# MCU.net
KiCad netlist of a schematic drawn in Altium Designer
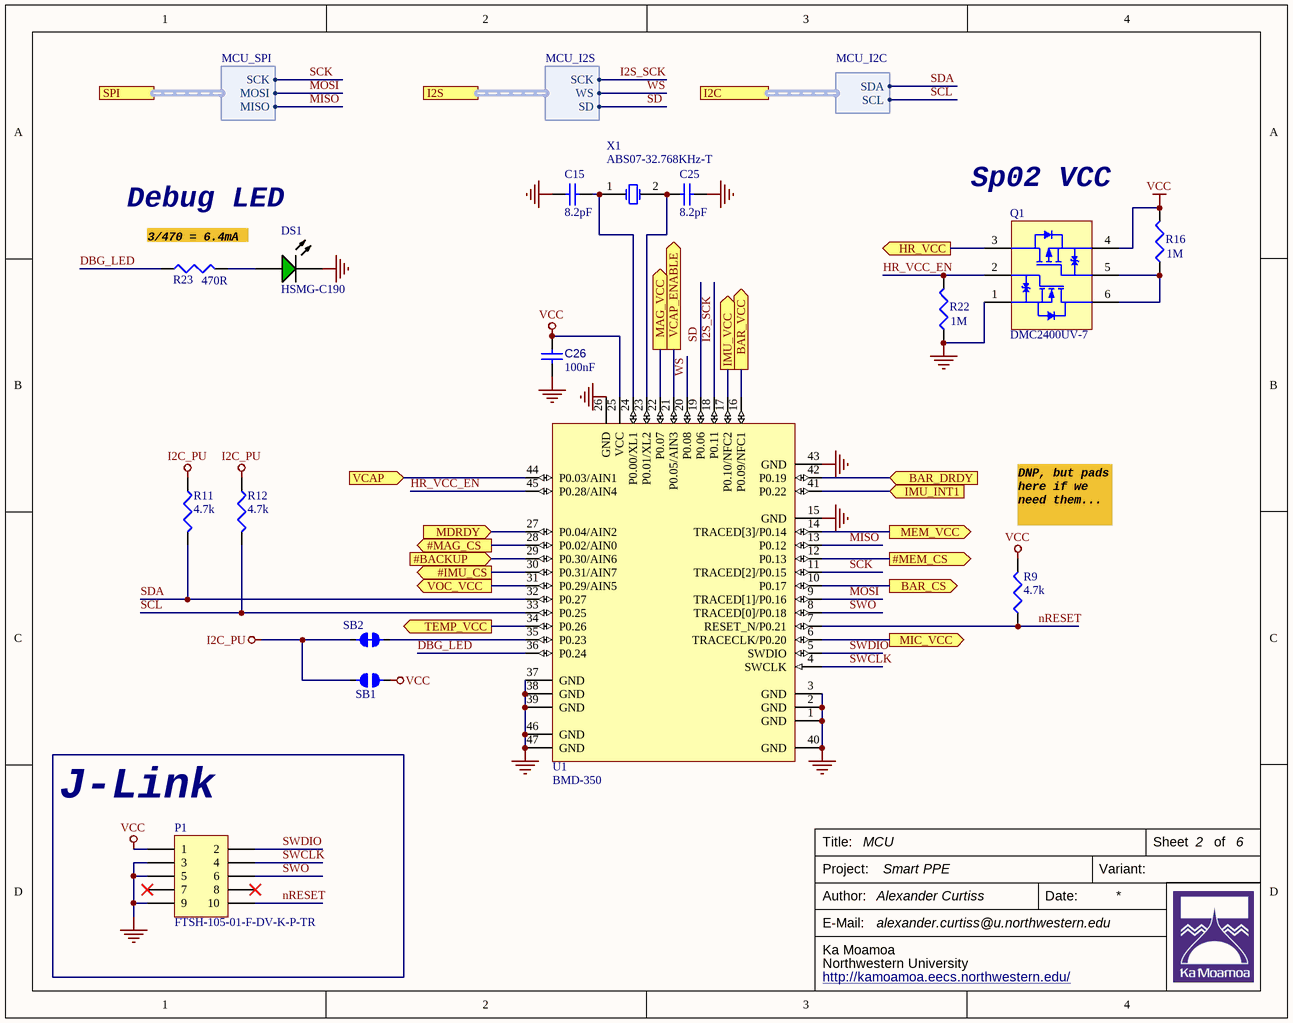
[diagram p0: MCU.SchDoc]

(export (version "E")
  (design (tool "Eeschema 10.0.6"))
  (components
    (comp (ref "C15")
      (value "8.2pF")
      (footprint "CAPC1005X56X25NL10T15")
      (fields
        (field (name "PART NUMBER") "04025A8R2JAT2A")
        (field (name "MANUFACTURER") "AVX Interconnect / Elco")
      )
      (libsource (lib "Altium Content Vault") (part "CAP"))
    )
    (comp (ref "C25")
      (value "8.2pF")
      (footprint "CAPC1005X56X25NL10T15")
      (fields
        (field (name "PART NUMBER") "04025A8R2JAT2A")
        (field (name "MANUFACTURER") "AVX Interconnect / Elco")
      )
      (libsource (lib "Altium Content Vault") (part "CAP"))
    )
    (comp (ref "C26")
      (value "100nF")
      (footprint "CAPC0402(1005)60_L")
      (description "Chip Capacitor, 100nF +/-20%, 25V, 0402, Thickness 0.6 mm")
      (fields (field (name "TOLERANCE") "10%") (field (name "Comment") "Capacitor 100nF +/-20% 25V 0402"))
      (libsource (lib "Ka Moamoa") (part "CAP-NP-2"))
    )
    (comp (ref "DS1")
      (value "HSMG-C190")
      (footprint "AVAG-HSMX-C190_V")
      (description "Chip LED, Green, 2.2 V, -40 to 85 degC, 2-Pin SMD, RoHS, Tape and Reel")
      (libsource (lib "Altium Content Vault") (part "LED-GREEN-AK-2"))
    )
    (comp (ref "P1")
      (value "FTSH-105-01-F-DV-K-P-TR")
      (footprint "FTSH-105-01-F-DV-K-P-TR-Footprint-1")
      (description "CONN HEADER SMD 10POS 1.27MM")
      (libsource (lib "Ka Moamoa") (part "FTSH-105-01-F-DV-K-P-TR"))
    )
    (comp (ref "Q1")
      (value "DMC2400UV-7")
      (footprint "DIOD-SOT563-6_V")
      (fields (field (name "MANUFACTURER") "Diodes Inc"))
      (libsource (lib "Altium Content Vault") (part "DIOD-DMC2400UV-SOT563-6"))
    )
    (comp (ref "R9")
      (value "4.7k")
      (footprint "RESC1608X55X25NL10T15")
      (description "Resistor 4.7kΩ 1% 0603")
      (fields (field (name "TOLERANCE") "1%"))
      (libsource (lib "Ka Moamoa") (part "RES"))
    )
    (comp (ref "R11")
      (value "4.7k")
      (footprint "RESC1608X55X25NL10T15")
      (description "Resistor 4.7kΩ 1% 0603")
      (fields (field (name "TOLERANCE") "1%"))
      (libsource (lib "Ka Moamoa") (part "RES"))
    )
    (comp (ref "R12")
      (value "4.7k")
      (footprint "RESC1608X55X25NL10T15")
      (description "Resistor 4.7kΩ 1% 0603")
      (fields (field (name "TOLERANCE") "1%"))
      (libsource (lib "Ka Moamoa") (part "RES"))
    )
    (comp (ref "R16")
      (value "1M")
      (footprint "RESC1608X55X25NL10T15")
      (description "Resistor =Value =Tolerance 0603")
      (fields (field (name "TOLERANCE") "1%"))
      (libsource (lib "Ka Moamoa") (part "RES"))
    )
    (comp (ref "R22")
      (value "1M")
      (footprint "RESC1608X55X25NL10T15")
      (description "Resistor =Value =Tolerance 0603")
      (fields (field (name "TOLERANCE") "1%"))
      (libsource (lib "Ka Moamoa") (part "RES"))
    )
    (comp (ref "R23")
      (value "470R")
      (footprint "RESC1608X55X25NL10T15")
      (description "Resistor 470Ω 1% 0603")
      (fields (field (name "TOLERANCE") "1%"))
      (libsource (lib "Ka Moamoa") (part "RES"))
    )
    (comp (ref "SB1")
      (value "Solder Bridge")
      (footprint "Solder Bridge-Footprint-1")
      (description "Normally open solder jumper")
      (libsource (lib "Ka Moamoa") (part "Solder Bridge"))
    )
    (comp (ref "SB2")
      (value "Solder Bridge NC")
      (footprint "Jumper NC-Footprint-1")
      (description "Normally closed solder jumper")
      (libsource (lib "Ka Moamoa") (part "Solder Bridge NC"))
    )
    (comp (ref "U1")
      (value "BMD-350")
      (footprint "BMD_LGA47S_865X640X150_CHIP")
      (description "u-blox BMD-350 Bluetooth 5 module")
      (fields (field (name "MANUFACTURER") "u-blox"))
      (libsource (lib "Ka Moamoa") (part "BMD-350"))
    )
    (comp (ref "X1")
      (value "ABS07-32.768KHz-T")
      (footprint "ABRA-ABS07-2_V")
      (description "Crystal, 32.768 kHz, 12.5 pF, -40 to 85 degC, SMD Low Profile 3.2 x 1.5 x 0.9 mm, Tape and Reel")
      (fields (field (name "MANUFACTURER") "Abracon"))
      (libsource (lib "Altium Content Vault") (part "ABRA-ABS07-2"))
    )
  )
  (nets
    (net (code "4") (name "/#BACKUP") (class "Default")
      (node (ref "U1") (pin "29") (pinfunction "P0.30/AIN6_29") (pintype "bidirectional"))
    )
    (net (code "5") (name "/#IMU_CS") (class "Default")
      (node (ref "U1") (pin "30") (pinfunction "P0.31/AIN7_30") (pintype "bidirectional"))
    )
    (net (code "6") (name "/#MAG_CS") (class "Default")
      (node (ref "U1") (pin "28") (pinfunction "P0.02/AIN0_28") (pintype "bidirectional"))
    )
    (net (code "7") (name "/#MEM_CS") (class "Default")
      (node (ref "U1") (pin "12") (pinfunction "P0.13_12") (pintype "bidirectional"))
    )
    (net (code "8") (name "/BAR_CS") (class "Default")
      (node (ref "U1") (pin "10") (pinfunction "P0.17_10") (pintype "bidirectional"))
    )
    (net (code "9") (name "/BAR_DRDY") (class "Default")
      (node (ref "U1") (pin "42") (pinfunction "P0.19_42") (pintype "bidirectional"))
    )
    (net (code "10") (name "/BAR_VCC") (class "Default")
      (node (ref "U1") (pin "16") (pinfunction "P0.09/NFC1_16") (pintype "bidirectional"))
    )
    (net (code "11") (name "/DBG_LED") (class "Default")
      (node (ref "R23") (pin "1") (pinfunction "1_1") (pintype "passive"))
      (node (ref "U1") (pin "36") (pinfunction "P0.24_36") (pintype "bidirectional"))
    )
    (net (code "12") (name "/HR_VCC") (class "Default")
      (node (ref "Q1") (pin "3") (pinfunction "D2_3") (pintype "passive"))
    )
    (net (code "13") (name "/HR_VCC_EN") (class "Default")
      (node (ref "Q1") (pin "2") (pinfunction "G1_2") (pintype "passive"))
      (node (ref "R22") (pin "2") (pinfunction "2_2") (pintype "passive"))
      (node (ref "U1") (pin "45") (pinfunction "P0.28/AIN4_45") (pintype "bidirectional"))
    )
    (net (code "14") (name "/I2S_SCK") (class "Default")
      (node (ref "U1") (pin "18") (pinfunction "P0.11_18") (pintype "bidirectional"))
    )
    (net (code "15") (name "/IMU_INT1") (class "Default")
      (node (ref "U1") (pin "41") (pinfunction "P0.22_41") (pintype "bidirectional"))
    )
    (net (code "16") (name "/IMU_VCC") (class "Default")
      (node (ref "U1") (pin "17") (pinfunction "P0.10/NFC2_17") (pintype "bidirectional"))
    )
    (net (code "17") (name "/MAG_VCC") (class "Default")
      (node (ref "U1") (pin "22") (pinfunction "P0.07_22") (pintype "bidirectional"))
    )
    (net (code "18") (name "/MDRDY") (class "Default")
      (node (ref "U1") (pin "27") (pinfunction "P0.04/AIN2_27") (pintype "bidirectional"))
    )
    (net (code "19") (name "/MEM_VCC") (class "Default")
      (node (ref "U1") (pin "14") (pinfunction "TRACED[3]/P0.14_14") (pintype "bidirectional"))
    )
    (net (code "20") (name "/MIC_VCC") (class "Default")
      (node (ref "U1") (pin "6") (pinfunction "TRACECLK/P0.20_6") (pintype "bidirectional"))
    )
    (net (code "21") (name "/MISO") (class "Default")
      (node (ref "U1") (pin "13") (pinfunction "P0.12_13") (pintype "bidirectional"))
    )
    (net (code "22") (name "/MOSI") (class "Default")
      (node (ref "U1") (pin "9") (pinfunction "TRACED[1]/P0.16_9") (pintype "bidirectional"))
    )
    (net (code "23") (name "/SCK") (class "Default")
      (node (ref "U1") (pin "11") (pinfunction "TRACED[2]/P0.15_11") (pintype "bidirectional"))
    )
    (net (code "24") (name "/SCL") (class "Default")
      (node (ref "R12") (pin "1") (pinfunction "1_1") (pintype "passive"))
      (node (ref "U1") (pin "33") (pinfunction "P0.25_33") (pintype "bidirectional"))
    )
    (net (code "25") (name "/SD") (class "Default")
      (node (ref "U1") (pin "19") (pinfunction "P0.06_19") (pintype "bidirectional"))
    )
    (net (code "26") (name "/SDA") (class "Default")
      (node (ref "R11") (pin "1") (pinfunction "1_1") (pintype "passive"))
      (node (ref "U1") (pin "32") (pinfunction "P0.27_32") (pintype "bidirectional"))
    )
    (net (code "27") (name "/SWCLK") (class "Default")
      (node (ref "P1") (pin "4") (pinfunction "4_4") (pintype "passive"))
      (node (ref "U1") (pin "4") (pinfunction "SWCLK_4") (pintype "input"))
    )
    (net (code "28") (name "/SWDIO") (class "Default")
      (node (ref "P1") (pin "2") (pinfunction "2_2") (pintype "passive"))
      (node (ref "U1") (pin "5") (pinfunction "SWDIO_5") (pintype "bidirectional"))
    )
    (net (code "29") (name "/SWO") (class "Default")
      (node (ref "P1") (pin "6") (pinfunction "6_6") (pintype "passive"))
      (node (ref "U1") (pin "8") (pinfunction "TRACED[0]/P0.18_8") (pintype "bidirectional"))
    )
    (net (code "30") (name "/TEMP_VCC") (class "Default")
      (node (ref "U1") (pin "34") (pinfunction "P0.26_34") (pintype "bidirectional"))
    )
    (net (code "31") (name "/VCAP") (class "Default")
      (node (ref "U1") (pin "44") (pinfunction "P0.03/AIN1_44") (pintype "bidirectional"))
    )
    (net (code "32") (name "/VCAP_ENABLE") (class "Default")
      (node (ref "U1") (pin "21") (pinfunction "P0.05/AIN3_21") (pintype "bidirectional"))
    )
    (net (code "33") (name "/VOC_VCC") (class "Default")
      (node (ref "U1") (pin "31") (pinfunction "P0.29/AIN5_31") (pintype "bidirectional"))
    )
    (net (code "34") (name "/WS") (class "Default")
      (node (ref "U1") (pin "20") (pinfunction "P0.08_20") (pintype "bidirectional"))
    )
    (net (code "35") (name "/nRESET") (class "Default")
      (node (ref "P1") (pin "10") (pinfunction "10_10") (pintype "passive"))
      (node (ref "R9") (pin "1") (pinfunction "1_1") (pintype "passive"))
      (node (ref "U1") (pin "7") (pinfunction "RESET_N/P0.21_7") (pintype "bidirectional"))
    )
    (net (code "39") (name "GND") (class "Default")
      (node (ref "C15") (pin "1") (pinfunction "1_1") (pintype "passive"))
      (node (ref "C25") (pin "1") (pinfunction "1_1") (pintype "passive"))
      (node (ref "C26") (pin "2") (pinfunction "2_2") (pintype "passive"))
      (node (ref "DS1") (pin "2") (pinfunction "K_2") (pintype "passive"))
      (node (ref "P1") (pin "3") (pinfunction "3_3") (pintype "passive"))
      (node (ref "P1") (pin "5") (pinfunction "5_5") (pintype "passive"))
      (node (ref "P1") (pin "9") (pinfunction "9_9") (pintype "passive"))
      (node (ref "Q1") (pin "1") (pinfunction "S1_1") (pintype "passive"))
      (node (ref "R22") (pin "1") (pinfunction "1_1") (pintype "passive"))
      (node (ref "U1") (pin "1") (pinfunction "GND_1") (pintype "power_in"))
      (node (ref "U1") (pin "15") (pinfunction "GND_15") (pintype "power_in"))
      (node (ref "U1") (pin "2") (pinfunction "GND_2") (pintype "power_in"))
      (node (ref "U1") (pin "26") (pinfunction "GND_26") (pintype "power_in"))
      (node (ref "U1") (pin "3") (pinfunction "GND_3") (pintype "power_in"))
      (node (ref "U1") (pin "37") (pinfunction "GND_37") (pintype "power_in"))
      (node (ref "U1") (pin "38") (pinfunction "GND_38") (pintype "power_in"))
      (node (ref "U1") (pin "39") (pinfunction "GND_39") (pintype "power_in"))
      (node (ref "U1") (pin "40") (pinfunction "GND_40") (pintype "power_in"))
      (node (ref "U1") (pin "43") (pinfunction "GND_43") (pintype "power_in"))
      (node (ref "U1") (pin "46") (pinfunction "GND_46") (pintype "power_in"))
      (node (ref "U1") (pin "47") (pinfunction "GND_47") (pintype "power_in"))
    )
    (net (code "40") (name "I2C_PU") (class "Default")
      (node (ref "R11") (pin "2") (pinfunction "2_2") (pintype "passive"))
      (node (ref "R12") (pin "2") (pinfunction "2_2") (pintype "passive"))
      (node (ref "SB1") (pin "1") (pinfunction "1_1") (pintype "passive"))
      (node (ref "SB2") (pin "1") (pinfunction "1_1") (pintype "passive"))
    )
    (net (code "41") (name "Net-(DS1-A)") (class "Default")
      (node (ref "DS1") (pin "1") (pinfunction "A_1") (pintype "passive"))
      (node (ref "R23") (pin "2") (pinfunction "2_2") (pintype "passive"))
    )
    (net (code "42") (name "Net-(Q1-D1)") (class "Default")
      (node (ref "Q1") (pin "5") (pinfunction "G2_5") (pintype "passive"))
      (node (ref "Q1") (pin "6") (pinfunction "D1_6") (pintype "passive"))
      (node (ref "R16") (pin "1") (pinfunction "1_1") (pintype "passive"))
    )
    (net (code "43") (name "Net-(U1-P0.00{slash}XL1)") (class "Default")
      (node (ref "C15") (pin "2") (pinfunction "2_2") (pintype "passive"))
      (node (ref "U1") (pin "24") (pinfunction "P0.00/XL1_24") (pintype "bidirectional"))
      (node (ref "X1") (pin "1") (pinfunction "X1_1") (pintype "passive"))
    )
    (net (code "44") (name "Net-(U1-P0.01{slash}XL2)") (class "Default")
      (node (ref "C25") (pin "2") (pinfunction "2_2") (pintype "passive"))
      (node (ref "U1") (pin "23") (pinfunction "P0.01/XL2_23") (pintype "bidirectional"))
      (node (ref "X1") (pin "2") (pinfunction "X2_2") (pintype "passive"))
    )
    (net (code "45") (name "Net-(U1-P0.23)") (class "Default")
      (node (ref "SB2") (pin "2") (pinfunction "2_2") (pintype "passive"))
      (node (ref "U1") (pin "35") (pinfunction "P0.23_35") (pintype "bidirectional"))
    )
    (net (code "46") (name "VCC") (class "Default")
      (node (ref "C26") (pin "1") (pinfunction "1_1") (pintype "passive"))
      (node (ref "P1") (pin "1") (pinfunction "1_1") (pintype "passive"))
      (node (ref "Q1") (pin "4") (pinfunction "S2_4") (pintype "passive"))
      (node (ref "R16") (pin "2") (pinfunction "2_2") (pintype "passive"))
      (node (ref "R9") (pin "2") (pinfunction "2_2") (pintype "passive"))
      (node (ref "SB1") (pin "2") (pinfunction "2_2") (pintype "passive"))
      (node (ref "U1") (pin "25") (pinfunction "VCC_25") (pintype "power_in"))
    )
    (net (code "47") (name "unconnected-(P1-Pad7)") (class "Default")
      (node (ref "P1") (pin "7") (pinfunction "7_7") (pintype "passive+no_connect"))
    )
    (net (code "48") (name "unconnected-(P1-Pad8)") (class "Default")
      (node (ref "P1") (pin "8") (pinfunction "8_8") (pintype "passive+no_connect"))
    )
  )
)
